# Sheet2.net
KiCad netlist of a schematic drawn in Altium Designer
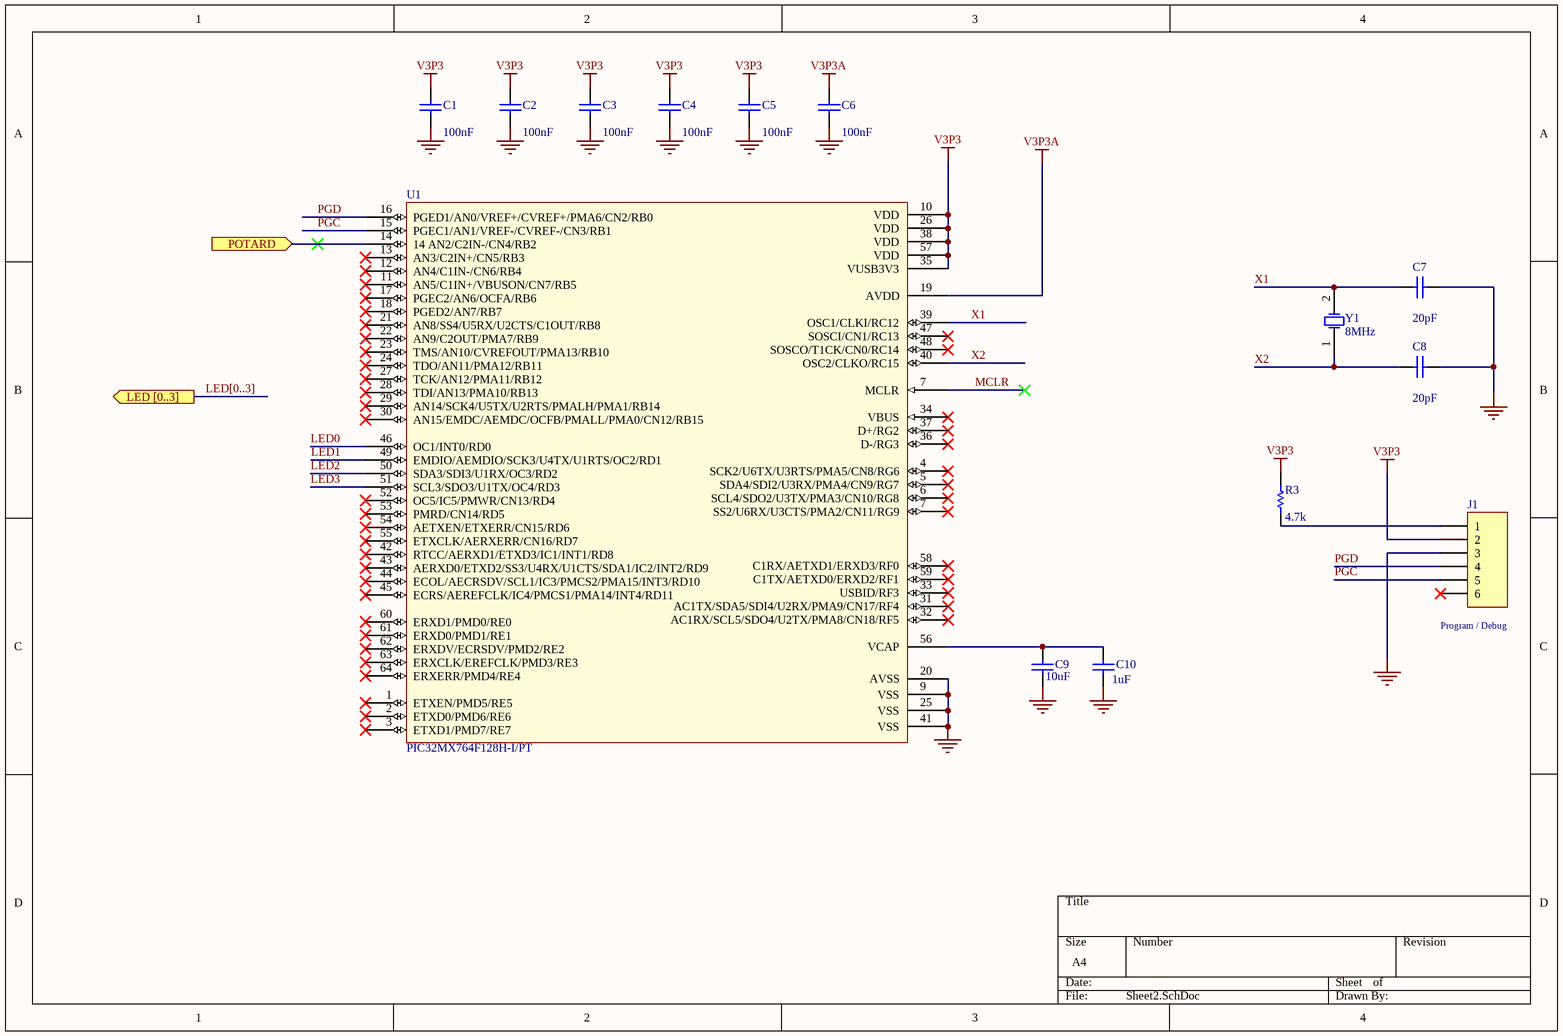
[diagram p0: Sheet2.SchDoc]

(export (version "E")
  (design (tool "Eeschema 10.0.6"))
  (components
    (comp (ref "C1")
      (value "100nF")
      (footprint "RAD-0.3")
      (description "Capacitor")
      (fields (field (name "PUBLISHER") "Altium Limited"))
      (libsource (lib "Miscellaneous Devices") (part "Cap"))
    )
    (comp (ref "C2")
      (value "100nF")
      (footprint "RAD-0.3")
      (description "Capacitor")
      (fields (field (name "Comment") "Cap") (field (name "PUBLISHER") "Altium Limited"))
      (libsource (lib "Miscellaneous Devices") (part "Cap"))
    )
    (comp (ref "C3")
      (value "100nF")
      (footprint "RAD-0.3")
      (description "Capacitor")
      (fields (field (name "Comment") "Cap") (field (name "PUBLISHER") "Altium Limited"))
      (libsource (lib "Miscellaneous Devices") (part "Cap"))
    )
    (comp (ref "C4")
      (value "100nF")
      (footprint "RAD-0.3")
      (description "Capacitor")
      (fields (field (name "Comment") "Cap") (field (name "PUBLISHER") "Altium Limited"))
      (libsource (lib "Miscellaneous Devices") (part "Cap"))
    )
    (comp (ref "C5")
      (value "100nF")
      (footprint "RAD-0.3")
      (description "Capacitor")
      (fields (field (name "Comment") "Cap") (field (name "PUBLISHER") "Altium Limited"))
      (libsource (lib "Miscellaneous Devices") (part "Cap"))
    )
    (comp (ref "C6")
      (value "100nF")
      (footprint "RAD-0.3")
      (description "Capacitor")
      (fields (field (name "Comment") "Cap") (field (name "PUBLISHER") "Altium Limited"))
      (libsource (lib "Miscellaneous Devices") (part "Cap"))
    )
    (comp (ref "C7")
      (value "20pF")
      (footprint "RAD-0.3")
      (description "Capacitor")
      (fields (field (name "Comment") "Cap") (field (name "PUBLISHER") "Altium Limited"))
      (libsource (lib "Miscellaneous Devices") (part "Cap"))
    )
    (comp (ref "C8")
      (value "20pF")
      (footprint "RAD-0.3")
      (description "Capacitor")
      (fields (field (name "Comment") "Cap") (field (name "PUBLISHER") "Altium Limited"))
      (libsource (lib "Miscellaneous Devices") (part "Cap"))
    )
    (comp (ref "C9")
      (value "10uF")
      (footprint "RAD-0.3")
      (description "Capacitor")
      (fields (field (name "Comment") "Cap") (field (name "PUBLISHER") "Altium Limited"))
      (libsource (lib "Miscellaneous Devices") (part "Cap"))
    )
    (comp (ref "C10")
      (value "1uF")
      (footprint "RAD-0.3")
      (description "Capacitor")
      (fields (field (name "Comment") "Cap") (field (name "PUBLISHER") "Altium Limited"))
      (libsource (lib "Miscellaneous Devices") (part "Cap"))
    )
    (comp (ref "J1")
      (value "Program / Debug")
      (footprint "HDR1X6")
      (description "Header, 6-Pin")
      (fields (field (name "PUBLISHER") "Altium Limited"))
      (libsource (lib "Miscellaneous Connectors") (part "Header 6"))
    )
    (comp (ref "R3")
      (value "4.7k")
      (footprint "AXIAL-0.3")
      (description "Resistor")
      (fields (field (name "Comment") "Res1") (field (name "PUBLISHER") "Altium Limited"))
      (libsource (lib "Miscellaneous Devices") (part "Res1"))
    )
    (comp (ref "U1")
      (value "PIC32MX764F128H-I/PT")
      (fields (field (name "COMMENT_1") "PIC32MX764F128H-I/PT"))
      (libsource (lib "PIC32_lib") (part "PIC32"))
    )
    (comp (ref "Y1")
      (value "8MHz")
      (footprint "R38")
      (description "Crystal Oscillator")
      (fields (field (name "PUBLISHER") "Altium Limited"))
      (libsource (lib "Miscellaneous Devices") (part "XTAL"))
    )
  )
  (nets
    (net (code "1") (name "/LED0") (class "Default")
      (node (ref "U1") (pin "46") (pinfunction "OC1/INT0/RD0_46") (pintype "bidirectional"))
    )
    (net (code "2") (name "/LED1") (class "Default")
      (node (ref "U1") (pin "49") (pinfunction "EMDIO/AEMDIO/SCK3/U4TX/U1RTS/OC2/RD1_49") (pintype "bidirectional"))
    )
    (net (code "3") (name "/LED2") (class "Default")
      (node (ref "U1") (pin "50") (pinfunction "SDA3/SDI3/U1RX/OC3/RD2_50") (pintype "bidirectional"))
    )
    (net (code "4") (name "/LED3") (class "Default")
      (node (ref "U1") (pin "51") (pinfunction "SCL3/SDO3/U1TX/OC4/RD3_51") (pintype "bidirectional"))
    )
    (net (code "6") (name "/MCLR") (class "Default")
      (node (ref "U1") (pin "7") (pinfunction "MCLR_7") (pintype "input+no_connect"))
    )
    (net (code "7") (name "/PGC") (class "Default")
      (node (ref "J1") (pin "5") (pinfunction "5_5") (pintype "passive"))
      (node (ref "U1") (pin "15") (pinfunction "PGEC1/AN1/VREF-/CVREF-/CN3/RB1_15") (pintype "bidirectional"))
    )
    (net (code "8") (name "/PGD") (class "Default")
      (node (ref "J1") (pin "4") (pinfunction "4_4") (pintype "passive"))
      (node (ref "U1") (pin "16") (pinfunction "PGED1/AN0/VREF+/CVREF+/PMA6/CN2/RB0_16") (pintype "bidirectional"))
    )
    (net (code "9") (name "/POTARD") (class "Default")
      (node (ref "U1") (pin "14") (pinfunction "14_AN2/C2IN-/CN4/RB2_14") (pintype "bidirectional+no_connect"))
    )
    (net (code "10") (name "/X1") (class "Default")
      (node (ref "C7") (pin "1") (pinfunction "1_1") (pintype "passive"))
      (node (ref "U1") (pin "39") (pinfunction "OSC1/CLKI/RC12_39") (pintype "bidirectional"))
      (node (ref "Y1") (pin "2") (pinfunction "OSC2_2") (pintype "passive"))
    )
    (net (code "11") (name "/X2") (class "Default")
      (node (ref "C8") (pin "1") (pinfunction "1_1") (pintype "passive"))
      (node (ref "U1") (pin "40") (pinfunction "OSC2/CLKO/RC15_40") (pintype "bidirectional"))
      (node (ref "Y1") (pin "1") (pinfunction "OSC1_1") (pintype "passive"))
    )
    (net (code "12") (name "<NO NET>") (class "Default")
      (node (ref "C1") (pin "1") (pinfunction "1_1") (pintype "passive"))
      (node (ref "C2") (pin "1") (pinfunction "1_1") (pintype "passive"))
      (node (ref "C3") (pin "1") (pinfunction "1_1") (pintype "passive"))
      (node (ref "C4") (pin "1") (pinfunction "1_1") (pintype "passive"))
      (node (ref "C5") (pin "1") (pinfunction "1_1") (pintype "passive"))
      (node (ref "C6") (pin "1") (pinfunction "1_1") (pintype "passive"))
    )
    (net (code "13") (name "GND") (class "Default")
      (node (ref "C10") (pin "2") (pinfunction "2_2") (pintype "passive"))
      (node (ref "C7") (pin "2") (pinfunction "2_2") (pintype "passive"))
      (node (ref "C8") (pin "2") (pinfunction "2_2") (pintype "passive"))
      (node (ref "C9") (pin "2") (pinfunction "2_2") (pintype "passive"))
      (node (ref "J1") (pin "3") (pinfunction "3_3") (pintype "passive"))
      (node (ref "U1") (pin "20") (pinfunction "AVSS_20") (pintype "passive"))
      (node (ref "U1") (pin "25") (pinfunction "VSS_25") (pintype "passive"))
      (node (ref "U1") (pin "41") (pinfunction "VSS_41") (pintype "passive"))
      (node (ref "U1") (pin "9") (pinfunction "VSS_9") (pintype "passive"))
    )
    (net (code "14") (name "Net-(J1-Pad1)") (class "Default")
      (node (ref "J1") (pin "1") (pinfunction "1_1") (pintype "passive"))
      (node (ref "R3") (pin "1") (pinfunction "1_1") (pintype "passive"))
    )
    (net (code "15") (name "Net-(U1-VCAP)") (class "Default")
      (node (ref "C10") (pin "1") (pinfunction "1_1") (pintype "passive"))
      (node (ref "C9") (pin "1") (pinfunction "1_1") (pintype "passive"))
      (node (ref "U1") (pin "56") (pinfunction "VCAP_56") (pintype "passive"))
    )
    (net (code "16") (name "V3P3") (class "Default")
      (node (ref "C1") (pin "2") (pinfunction "2_2") (pintype "passive"))
      (node (ref "C2") (pin "2") (pinfunction "2_2") (pintype "passive"))
      (node (ref "C3") (pin "2") (pinfunction "2_2") (pintype "passive"))
      (node (ref "C4") (pin "2") (pinfunction "2_2") (pintype "passive"))
      (node (ref "C5") (pin "2") (pinfunction "2_2") (pintype "passive"))
      (node (ref "J1") (pin "2") (pinfunction "2_2") (pintype "passive"))
      (node (ref "R3") (pin "2") (pinfunction "2_2") (pintype "passive"))
      (node (ref "U1") (pin "10") (pinfunction "VDD_10") (pintype "passive"))
      (node (ref "U1") (pin "26") (pinfunction "VDD_26") (pintype "passive"))
      (node (ref "U1") (pin "35") (pinfunction "VUSB3V3_35") (pintype "passive"))
      (node (ref "U1") (pin "38") (pinfunction "VDD_38") (pintype "passive"))
      (node (ref "U1") (pin "57") (pinfunction "VDD_57") (pintype "passive"))
    )
    (net (code "17") (name "V3P3A") (class "Default")
      (node (ref "C6") (pin "2") (pinfunction "2_2") (pintype "passive"))
      (node (ref "U1") (pin "19") (pinfunction "AVDD_19") (pintype "passive"))
    )
    (net (code "18") (name "unconnected-(J1-Pad6)") (class "Default")
      (node (ref "J1") (pin "6") (pinfunction "6_6") (pintype "passive+no_connect"))
    )
    (net (code "19") (name "unconnected-(U1-AC1RX{slash}SCL5{slash}SDO4{slash}U2TX{slash}PMA8{slash}CN18{slash}RF5-Pad32)") (class "Default")
      (node (ref "U1") (pin "32") (pinfunction "AC1RX/SCL5/SDO4/U2TX/PMA8/CN18/RF5_32") (pintype "bidirectional+no_connect"))
    )
    (net (code "20") (name "unconnected-(U1-AC1TX{slash}SDA5{slash}SDI4{slash}U2RX{slash}PMA9{slash}CN17{slash}RF4-Pad31)") (class "Default")
      (node (ref "U1") (pin "31") (pinfunction "AC1TX/SDA5/SDI4/U2RX/PMA9/CN17/RF4_31") (pintype "bidirectional+no_connect"))
    )
    (net (code "21") (name "unconnected-(U1-AERXD0{slash}ETXD2{slash}SS3{slash}U4RX{slash}U1CTS{slash}SDA1{slash}IC2{slash}INT2{slash}RD9-Pad43)") (class "Default")
      (node (ref "U1") (pin "43") (pinfunction "AERXD0/ETXD2/SS3/U4RX/U1CTS/SDA1/IC2/INT2/RD9_43") (pintype "bidirectional+no_connect"))
    )
    (net (code "22") (name "unconnected-(U1-AETXEN{slash}ETXERR{slash}CN15{slash}RD6-Pad54)") (class "Default")
      (node (ref "U1") (pin "54") (pinfunction "AETXEN/ETXERR/CN15/RD6_54") (pintype "bidirectional+no_connect"))
    )
    (net (code "23") (name "unconnected-(U1-AN3{slash}C2IN+{slash}CN5{slash}RB3-Pad13)") (class "Default")
      (node (ref "U1") (pin "13") (pinfunction "AN3/C2IN+/CN5/RB3_13") (pintype "bidirectional+no_connect"))
    )
    (net (code "24") (name "unconnected-(U1-AN4{slash}C1IN-{slash}CN6{slash}RB4-Pad12)") (class "Default")
      (node (ref "U1") (pin "12") (pinfunction "AN4/C1IN-/CN6/RB4_12") (pintype "bidirectional+no_connect"))
    )
    (net (code "25") (name "unconnected-(U1-AN5{slash}C1IN+{slash}VBUSON{slash}CN7{slash}RB5-Pad11)") (class "Default")
      (node (ref "U1") (pin "11") (pinfunction "AN5/C1IN+/VBUSON/CN7/RB5_11") (pintype "bidirectional+no_connect"))
    )
    (net (code "26") (name "unconnected-(U1-AN8{slash}SS4{slash}U5RX{slash}U2CTS{slash}C1OUT{slash}RB8-Pad21)") (class "Default")
      (node (ref "U1") (pin "21") (pinfunction "AN8/SS4/U5RX/U2CTS/C1OUT/RB8_21") (pintype "bidirectional+no_connect"))
    )
    (net (code "27") (name "unconnected-(U1-AN9{slash}C2OUT{slash}PMA7{slash}RB9-Pad22)") (class "Default")
      (node (ref "U1") (pin "22") (pinfunction "AN9/C2OUT/PMA7/RB9_22") (pintype "bidirectional+no_connect"))
    )
    (net (code "28") (name "unconnected-(U1-AN14{slash}SCK4{slash}U5TX{slash}U2RTS{slash}PMALH{slash}PMA1{slash}RB14-Pad29)") (class "Default")
      (node (ref "U1") (pin "29") (pinfunction "AN14/SCK4/U5TX/U2RTS/PMALH/PMA1/RB14_29") (pintype "bidirectional+no_connect"))
    )
    (net (code "29") (name "unconnected-(U1-AN15{slash}EMDC{slash}AEMDC{slash}OCFB{slash}PMALL{slash}PMA0{slash}CN12{slash}RB15-Pad30)") (class "Default")
      (node (ref "U1") (pin "30") (pinfunction "AN15/EMDC/AEMDC/OCFB/PMALL/PMA0/CN12/RB15_30") (pintype "bidirectional+no_connect"))
    )
    (net (code "30") (name "unconnected-(U1-C1RX{slash}AETXD1{slash}ERXD3{slash}RF0-Pad58)") (class "Default")
      (node (ref "U1") (pin "58") (pinfunction "C1RX/AETXD1/ERXD3/RF0_58") (pintype "bidirectional+no_connect"))
    )
    (net (code "31") (name "unconnected-(U1-C1TX{slash}AETXD0{slash}ERXD2{slash}RF1-Pad59)") (class "Default")
      (node (ref "U1") (pin "59") (pinfunction "C1TX/AETXD0/ERXD2/RF1_59") (pintype "bidirectional+no_connect"))
    )
    (net (code "32") (name "unconnected-(U1-D+{slash}RG2-Pad37)") (class "Default")
      (node (ref "U1") (pin "37") (pinfunction "D+/RG2_37") (pintype "bidirectional+no_connect"))
    )
    (net (code "33") (name "unconnected-(U1-D-{slash}RG3-Pad36)") (class "Default")
      (node (ref "U1") (pin "36") (pinfunction "D-/RG3_36") (pintype "bidirectional+no_connect"))
    )
    (net (code "34") (name "unconnected-(U1-ECOL{slash}AECRSDV{slash}SCL1{slash}IC3{slash}PMCS2{slash}PMA15{slash}INT3{slash}RD10-Pad44)") (class "Default")
      (node (ref "U1") (pin "44") (pinfunction "ECOL/AECRSDV/SCL1/IC3/PMCS2/PMA15/INT3/RD10_44") (pintype "bidirectional+no_connect"))
    )
    (net (code "35") (name "unconnected-(U1-ECRS{slash}AEREFCLK{slash}IC4{slash}PMCS1{slash}PMA14{slash}INT4{slash}RD11-Pad45)") (class "Default")
      (node (ref "U1") (pin "45") (pinfunction "ECRS/AEREFCLK/IC4/PMCS1/PMA14/INT4/RD11_45") (pintype "bidirectional+no_connect"))
    )
    (net (code "36") (name "unconnected-(U1-ERXCLK{slash}EREFCLK{slash}PMD3{slash}RE3-Pad63)") (class "Default")
      (node (ref "U1") (pin "63") (pinfunction "ERXCLK/EREFCLK/PMD3/RE3_63") (pintype "bidirectional+no_connect"))
    )
    (net (code "37") (name "unconnected-(U1-ERXD0{slash}PMD1{slash}RE1-Pad61)") (class "Default")
      (node (ref "U1") (pin "61") (pinfunction "ERXD0/PMD1/RE1_61") (pintype "bidirectional+no_connect"))
    )
    (net (code "38") (name "unconnected-(U1-ERXD1{slash}PMD0{slash}RE0-Pad60)") (class "Default")
      (node (ref "U1") (pin "60") (pinfunction "ERXD1/PMD0/RE0_60") (pintype "bidirectional+no_connect"))
    )
    (net (code "39") (name "unconnected-(U1-ERXDV{slash}ECRSDV{slash}PMD2{slash}RE2-Pad62)") (class "Default")
      (node (ref "U1") (pin "62") (pinfunction "ERXDV/ECRSDV/PMD2/RE2_62") (pintype "bidirectional+no_connect"))
    )
    (net (code "40") (name "unconnected-(U1-ERXERR{slash}PMD4{slash}RE4-Pad64)") (class "Default")
      (node (ref "U1") (pin "64") (pinfunction "ERXERR/PMD4/RE4_64") (pintype "bidirectional+no_connect"))
    )
    (net (code "41") (name "unconnected-(U1-ETXCLK{slash}AERXERR{slash}CN16{slash}RD7-Pad55)") (class "Default")
      (node (ref "U1") (pin "55") (pinfunction "ETXCLK/AERXERR/CN16/RD7_55") (pintype "bidirectional+no_connect"))
    )
    (net (code "42") (name "unconnected-(U1-ETXD0{slash}PMD6{slash}RE6-Pad2)") (class "Default")
      (node (ref "U1") (pin "2") (pinfunction "ETXD0/PMD6/RE6_2") (pintype "bidirectional+no_connect"))
    )
    (net (code "43") (name "unconnected-(U1-ETXD1{slash}PMD7{slash}RE7-Pad3)") (class "Default")
      (node (ref "U1") (pin "3") (pinfunction "ETXD1/PMD7/RE7_3") (pintype "bidirectional+no_connect"))
    )
    (net (code "44") (name "unconnected-(U1-ETXEN{slash}PMD5{slash}RE5-Pad1)") (class "Default")
      (node (ref "U1") (pin "1") (pinfunction "ETXEN/PMD5/RE5_1") (pintype "bidirectional+no_connect"))
    )
    (net (code "45") (name "unconnected-(U1-OC5{slash}IC5{slash}PMWR{slash}CN13{slash}RD4-Pad52)") (class "Default")
      (node (ref "U1") (pin "52") (pinfunction "OC5/IC5/PMWR/CN13/RD4_52") (pintype "bidirectional+no_connect"))
    )
    (net (code "46") (name "unconnected-(U1-PGEC2{slash}AN6{slash}OCFA{slash}RB6-Pad17)") (class "Default")
      (node (ref "U1") (pin "17") (pinfunction "PGEC2/AN6/OCFA/RB6_17") (pintype "bidirectional+no_connect"))
    )
    (net (code "47") (name "unconnected-(U1-PGED2{slash}AN7{slash}RB7-Pad18)") (class "Default")
      (node (ref "U1") (pin "18") (pinfunction "PGED2/AN7/RB7_18") (pintype "bidirectional+no_connect"))
    )
    (net (code "48") (name "unconnected-(U1-PMRD{slash}CN14{slash}RD5-Pad53)") (class "Default")
      (node (ref "U1") (pin "53") (pinfunction "PMRD/CN14/RD5_53") (pintype "bidirectional+no_connect"))
    )
    (net (code "49") (name "unconnected-(U1-RTCC{slash}AERXD1{slash}ETXD3{slash}IC1{slash}INT1{slash}RD8-Pad42)") (class "Default")
      (node (ref "U1") (pin "42") (pinfunction "RTCC/AERXD1/ETXD3/IC1/INT1/RD8_42") (pintype "bidirectional+no_connect"))
    )
    (net (code "50") (name "unconnected-(U1-SCK2{slash}U6TX{slash}U3RTS{slash}PMA5{slash}CN8{slash}RG6-Pad4)") (class "Default")
      (node (ref "U1") (pin "4") (pinfunction "SCK2/U6TX/U3RTS/PMA5/CN8/RG6_4") (pintype "bidirectional+no_connect"))
    )
    (net (code "51") (name "unconnected-(U1-SCL4{slash}SDO2{slash}U3TX{slash}PMA3{slash}CN10{slash}RG8-Pad6)") (class "Default")
      (node (ref "U1") (pin "6") (pinfunction "SCL4/SDO2/U3TX/PMA3/CN10/RG8_6") (pintype "bidirectional+no_connect"))
    )
    (net (code "52") (name "unconnected-(U1-SDA4{slash}SDI2{slash}U3RX{slash}PMA4{slash}CN9{slash}RG7-Pad5)") (class "Default")
      (node (ref "U1") (pin "5") (pinfunction "SDA4/SDI2/U3RX/PMA4/CN9/RG7_5") (pintype "bidirectional+no_connect"))
    )
    (net (code "53") (name "unconnected-(U1-SOSCI{slash}CN1{slash}RC13-Pad47)") (class "Default")
      (node (ref "U1") (pin "47") (pinfunction "SOSCI/CN1/RC13_47") (pintype "bidirectional+no_connect"))
    )
    (net (code "54") (name "unconnected-(U1-SOSCO{slash}T1CK{slash}CN0{slash}RC14-Pad48)") (class "Default")
      (node (ref "U1") (pin "48") (pinfunction "SOSCO/T1CK/CN0/RC14_48") (pintype "bidirectional+no_connect"))
    )
    (net (code "55") (name "unconnected-(U1-SS2{slash}U6RX{slash}U3CTS{slash}PMA2{slash}CN11{slash}RG9-Pad7)") (class "Default")
      (node (ref "U1") (pin "7") (pinfunction "SS2/U6RX/U3CTS/PMA2/CN11/RG9_7") (pintype "bidirectional+no_connect"))
    )
    (net (code "56") (name "unconnected-(U1-TCK{slash}AN12{slash}PMA11{slash}RB12-Pad27)") (class "Default")
      (node (ref "U1") (pin "27") (pinfunction "TCK/AN12/PMA11/RB12_27") (pintype "bidirectional+no_connect"))
    )
    (net (code "57") (name "unconnected-(U1-TDI{slash}AN13{slash}PMA10{slash}RB13-Pad28)") (class "Default")
      (node (ref "U1") (pin "28") (pinfunction "TDI/AN13/PMA10/RB13_28") (pintype "bidirectional+no_connect"))
    )
    (net (code "58") (name "unconnected-(U1-TDO{slash}AN11{slash}PMA12{slash}RB11-Pad24)") (class "Default")
      (node (ref "U1") (pin "24") (pinfunction "TDO/AN11/PMA12/RB11_24") (pintype "bidirectional+no_connect"))
    )
    (net (code "59") (name "unconnected-(U1-TMS{slash}AN10{slash}CVREFOUT{slash}PMA13{slash}RB10-Pad23)") (class "Default")
      (node (ref "U1") (pin "23") (pinfunction "TMS/AN10/CVREFOUT/PMA13/RB10_23") (pintype "bidirectional+no_connect"))
    )
    (net (code "60") (name "unconnected-(U1-USBID{slash}RF3-Pad33)") (class "Default")
      (node (ref "U1") (pin "33") (pinfunction "USBID/RF3_33") (pintype "bidirectional+no_connect"))
    )
    (net (code "61") (name "unconnected-(U1-VBUS-Pad34)") (class "Default")
      (node (ref "U1") (pin "34") (pinfunction "VBUS_34") (pintype "input+no_connect"))
    )
  )
)
